# power.net
KiCad netlist of a schematic drawn in Altium Designer
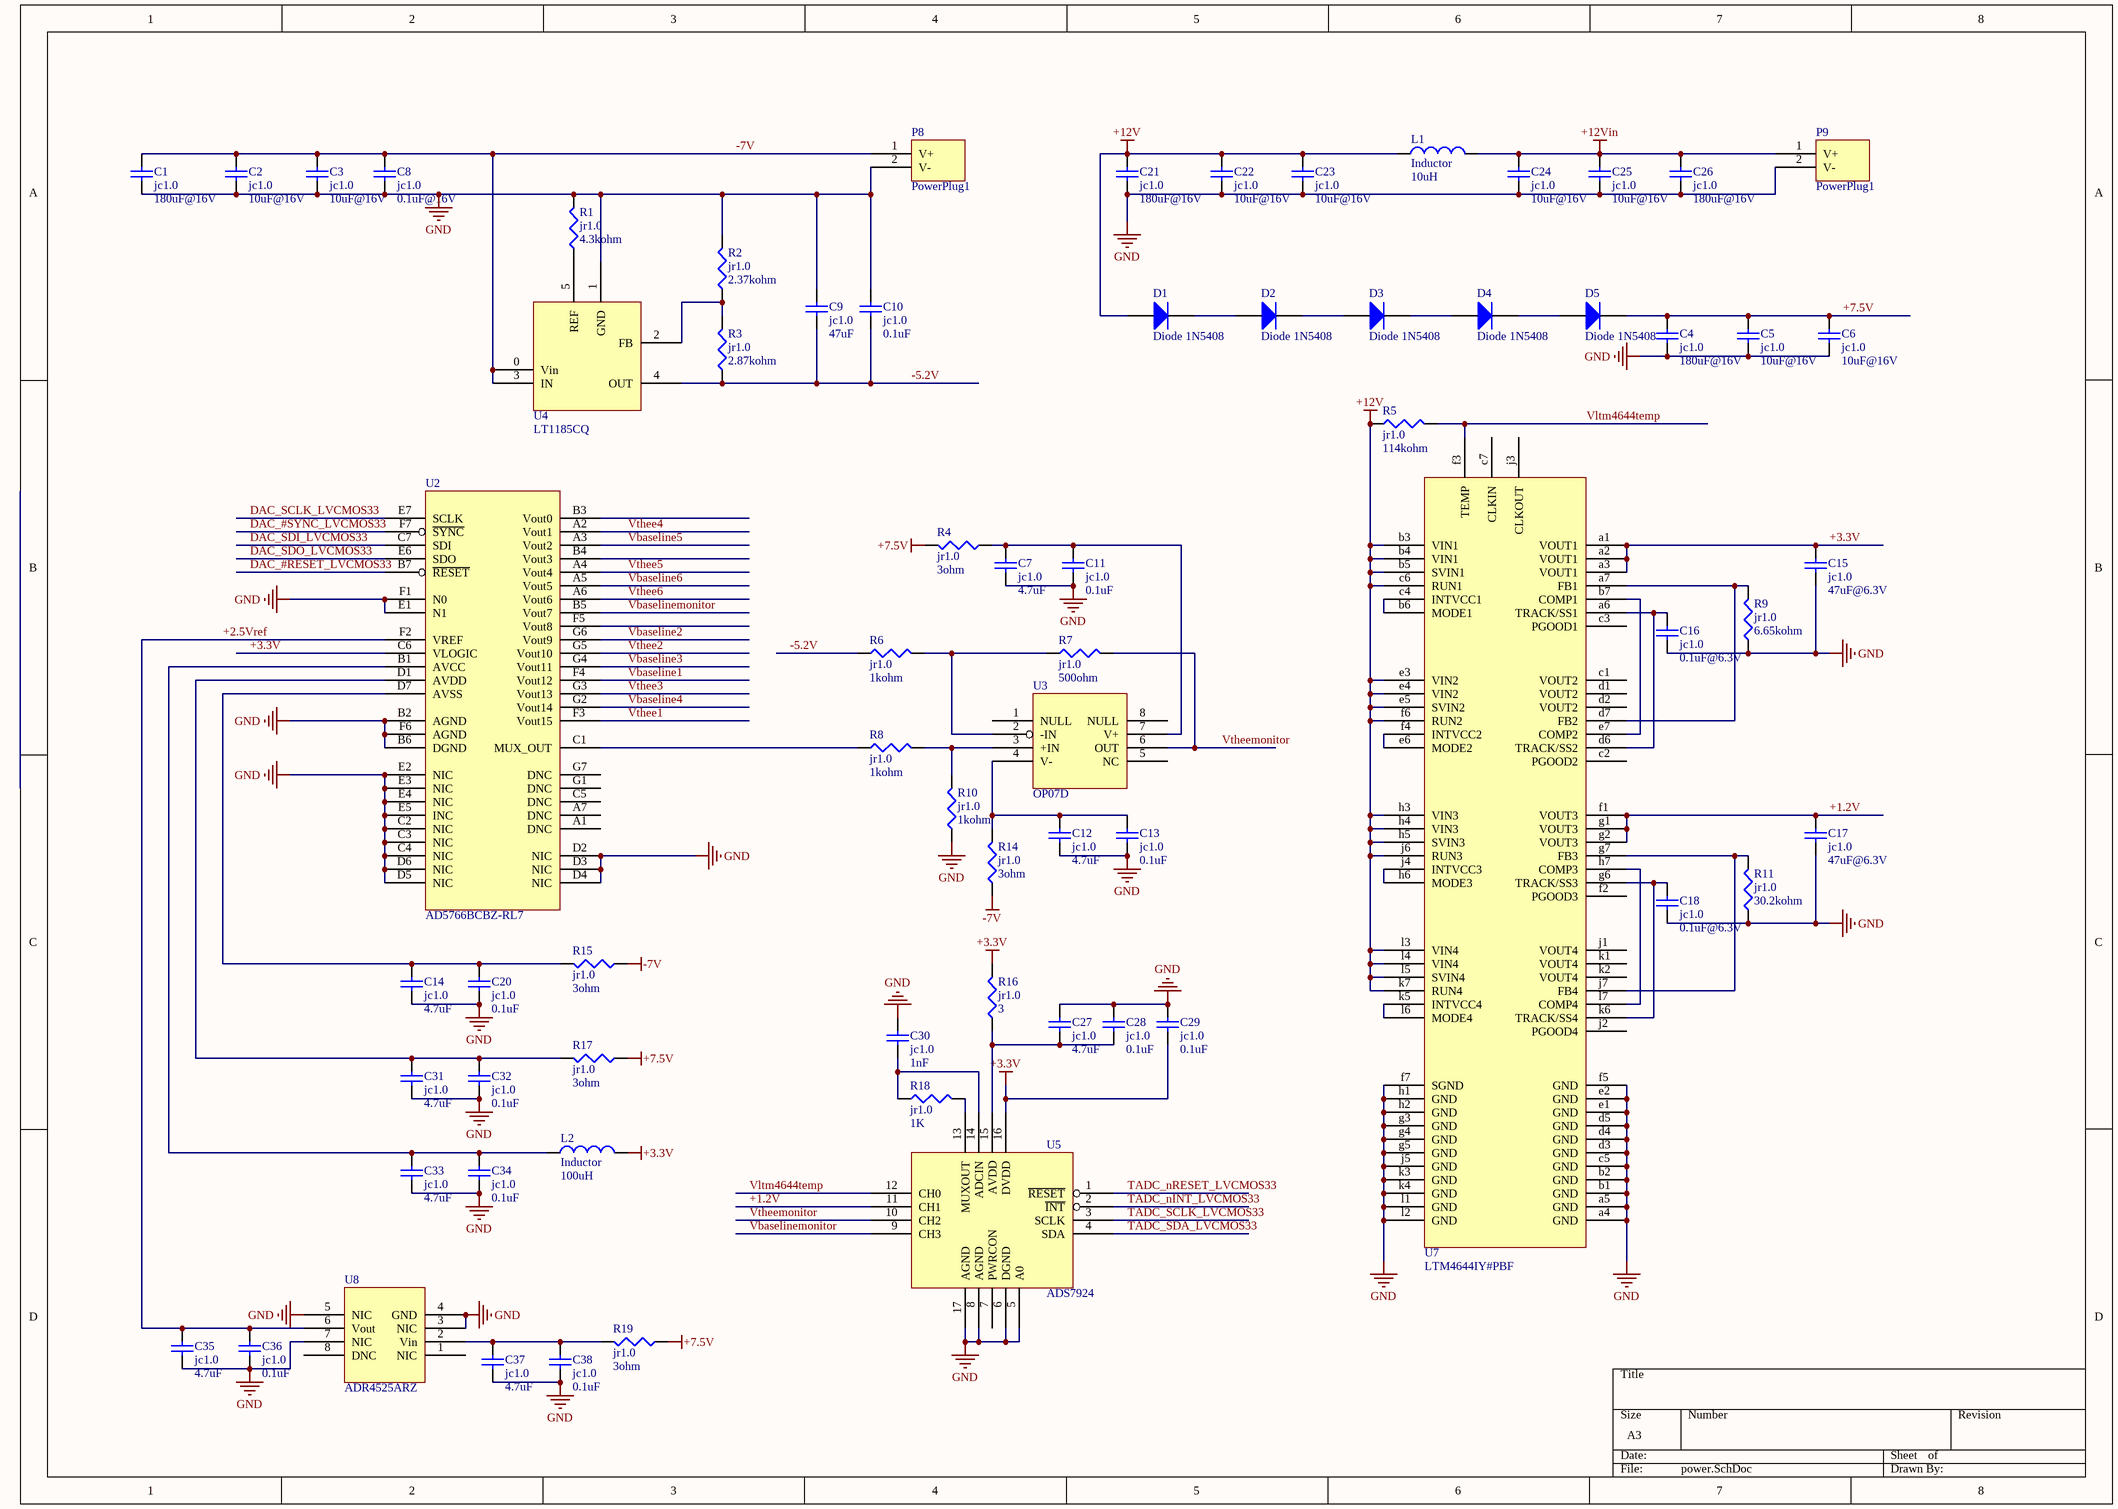
[diagram p0: power.SchDoc]

(export (version "E")
  (design (tool "Eeschema 10.0.6"))
  (components
    (comp (ref "C1")
      (value "jc1.0")
      (footprint "2220")
      (description "Capacitor")
      (fields (field (name "ALTIUM_VALUE") "180uF@16V") (field (name "PUBLISHER") "Altium Limited"))
      (libsource (lib "LIB01DXP2006SchLib") (part "Cap"))
    )
    (comp (ref "C2")
      (value "jc1.0")
      (footprint "2220")
      (description "Capacitor")
      (fields (field (name "ALTIUM_VALUE") "10uF@16V") (field (name "PUBLISHER") "Altium Limited"))
      (libsource (lib "LIB01DXP2006SchLib") (part "Cap"))
    )
    (comp (ref "C3")
      (value "jc1.0")
      (footprint "2220")
      (description "Capacitor")
      (fields (field (name "ALTIUM_VALUE") "10uF@16V") (field (name "PUBLISHER") "Altium Limited"))
      (libsource (lib "LIB01DXP2006SchLib") (part "Cap"))
    )
    (comp (ref "C4")
      (value "jc1.0")
      (footprint "2220")
      (description "Capacitor")
      (fields (field (name "ALTIUM_VALUE") "180uF@16V") (field (name "PUBLISHER") "Altium Limited"))
      (libsource (lib "LIB01DXP2006SchLib") (part "Cap"))
    )
    (comp (ref "C5")
      (value "jc1.0")
      (footprint "2220")
      (description "Capacitor")
      (fields (field (name "ALTIUM_VALUE") "10uF@16V") (field (name "PUBLISHER") "Altium Limited"))
      (libsource (lib "LIB01DXP2006SchLib") (part "Cap"))
    )
    (comp (ref "C6")
      (value "jc1.0")
      (footprint "2220")
      (description "Capacitor")
      (fields (field (name "ALTIUM_VALUE") "10uF@16V") (field (name "PUBLISHER") "Altium Limited"))
      (libsource (lib "LIB01DXP2006SchLib") (part "Cap"))
    )
    (comp (ref "C7")
      (value "jc1.0")
      (footprint "0603")
      (description "Capacitor")
      (fields (field (name "ALTIUM_VALUE") "4.7uF") (field (name "PUBLISHER") "Altium Limited"))
      (libsource (lib "LIB01DXP2006SchLib") (part "Cap"))
    )
    (comp (ref "C8")
      (value "jc1.0")
      (footprint "0805")
      (description "Capacitor")
      (fields (field (name "ALTIUM_VALUE") "0.1uF@16V") (field (name "PUBLISHER") "Altium Limited"))
      (libsource (lib "LIB01DXP2006SchLib") (part "Cap"))
    )
    (comp (ref "C9")
      (value "jc1.0")
      (footprint "2220")
      (description "Capacitor")
      (fields (field (name "ALTIUM_VALUE") "47uF") (field (name "PUBLISHER") "Altium Limited"))
      (libsource (lib "LIB01DXP2006SchLib") (part "Cap"))
    )
    (comp (ref "C10")
      (value "jc1.0")
      (footprint "2220")
      (description "Capacitor")
      (fields (field (name "ALTIUM_VALUE") "0.1uF") (field (name "PUBLISHER") "Altium Limited"))
      (libsource (lib "LIB01DXP2006SchLib") (part "Cap"))
    )
    (comp (ref "C11")
      (value "jc1.0")
      (footprint "0603")
      (description "Capacitor")
      (fields (field (name "ALTIUM_VALUE") "0.1uF") (field (name "PUBLISHER") "Altium Limited"))
      (libsource (lib "LIB01DXP2006SchLib") (part "Cap"))
    )
    (comp (ref "C12")
      (value "jc1.0")
      (footprint "0603")
      (description "Capacitor")
      (fields (field (name "ALTIUM_VALUE") "4.7uF") (field (name "PUBLISHER") "Altium Limited"))
      (libsource (lib "LIB01DXP2006SchLib") (part "Cap"))
    )
    (comp (ref "C13")
      (value "jc1.0")
      (footprint "0603")
      (description "Capacitor")
      (fields (field (name "ALTIUM_VALUE") "0.1uF") (field (name "PUBLISHER") "Altium Limited"))
      (libsource (lib "LIB01DXP2006SchLib") (part "Cap"))
    )
    (comp (ref "C14")
      (value "jc1.0")
      (footprint "0603")
      (description "Capacitor")
      (fields (field (name "ALTIUM_VALUE") "4.7uF") (field (name "PUBLISHER") "Altium Limited"))
      (libsource (lib "LIB01DXP2006SchLib") (part "Cap"))
    )
    (comp (ref "C15")
      (value "jc1.0")
      (footprint "0805")
      (description "Capacitor")
      (fields (field (name "ALTIUM_VALUE") "47uF@6.3V") (field (name "PUBLISHER") "Altium Limited"))
      (libsource (lib "LIB01DXP2006SchLib") (part "Cap"))
    )
    (comp (ref "C16")
      (value "jc1.0")
      (footprint "0402")
      (description "Capacitor")
      (fields (field (name "ALTIUM_VALUE") "0.1uF@6.3V") (field (name "PUBLISHER") "Altium Limited"))
      (libsource (lib "LIB01DXP2006SchLib") (part "Cap"))
    )
    (comp (ref "C17")
      (value "jc1.0")
      (footprint "0805")
      (description "Capacitor")
      (fields (field (name "ALTIUM_VALUE") "47uF@6.3V") (field (name "PUBLISHER") "Altium Limited"))
      (libsource (lib "LIB01DXP2006SchLib") (part "Cap"))
    )
    (comp (ref "C18")
      (value "jc1.0")
      (footprint "0402")
      (description "Capacitor")
      (fields (field (name "ALTIUM_VALUE") "0.1uF@6.3V") (field (name "PUBLISHER") "Altium Limited"))
      (libsource (lib "LIB01DXP2006SchLib") (part "Cap"))
    )
    (comp (ref "C20")
      (value "jc1.0")
      (footprint "0603")
      (description "Capacitor")
      (fields (field (name "ALTIUM_VALUE") "0.1uF") (field (name "PUBLISHER") "Altium Limited"))
      (libsource (lib "LIB01DXP2006SchLib") (part "Cap"))
    )
    (comp (ref "C21")
      (value "jc1.0")
      (footprint "2220")
      (description "Capacitor")
      (fields (field (name "ALTIUM_VALUE") "180uF@16V") (field (name "PUBLISHER") "Altium Limited"))
      (libsource (lib "LIB01DXP2006SchLib") (part "Cap"))
    )
    (comp (ref "C22")
      (value "jc1.0")
      (footprint "2220")
      (description "Capacitor")
      (fields (field (name "ALTIUM_VALUE") "10uF@16V") (field (name "PUBLISHER") "Altium Limited"))
      (libsource (lib "LIB01DXP2006SchLib") (part "Cap"))
    )
    (comp (ref "C23")
      (value "jc1.0")
      (footprint "2220")
      (description "Capacitor")
      (fields (field (name "ALTIUM_VALUE") "10uF@16V") (field (name "PUBLISHER") "Altium Limited"))
      (libsource (lib "LIB01DXP2006SchLib") (part "Cap"))
    )
    (comp (ref "C24")
      (value "jc1.0")
      (footprint "2220")
      (description "Capacitor")
      (fields (field (name "ALTIUM_VALUE") "10uF@16V") (field (name "PUBLISHER") "Altium Limited"))
      (libsource (lib "LIB01DXP2006SchLib") (part "Cap"))
    )
    (comp (ref "C25")
      (value "jc1.0")
      (footprint "2220")
      (description "Capacitor")
      (fields (field (name "ALTIUM_VALUE") "10uF@16V") (field (name "PUBLISHER") "Altium Limited"))
      (libsource (lib "LIB01DXP2006SchLib") (part "Cap"))
    )
    (comp (ref "C26")
      (value "jc1.0")
      (footprint "2220")
      (description "Capacitor")
      (fields (field (name "ALTIUM_VALUE") "180uF@16V") (field (name "PUBLISHER") "Altium Limited"))
      (libsource (lib "LIB01DXP2006SchLib") (part "Cap"))
    )
    (comp (ref "C27")
      (value "jc1.0")
      (footprint "0201")
      (description "Capacitor")
      (fields (field (name "ALTIUM_VALUE") "4.7uF") (field (name "PUBLISHER") "Altium Limited"))
      (libsource (lib "LIB01DXP2006SchLib") (part "Cap"))
    )
    (comp (ref "C28")
      (value "jc1.0")
      (footprint "0201")
      (description "Capacitor")
      (fields (field (name "ALTIUM_VALUE") "0.1uF") (field (name "PUBLISHER") "Altium Limited"))
      (libsource (lib "LIB01DXP2006SchLib") (part "Cap"))
    )
    (comp (ref "C29")
      (value "jc1.0")
      (footprint "0201")
      (description "Capacitor")
      (fields (field (name "ALTIUM_VALUE") "0.1uF") (field (name "PUBLISHER") "Altium Limited"))
      (libsource (lib "LIB01DXP2006SchLib") (part "Cap"))
    )
    (comp (ref "C30")
      (value "jc1.0")
      (footprint "0201")
      (description "Capacitor")
      (fields (field (name "ALTIUM_VALUE") "1nF") (field (name "PUBLISHER") "Altium Limited"))
      (libsource (lib "LIB01DXP2006SchLib") (part "Cap"))
    )
    (comp (ref "C31")
      (value "jc1.0")
      (footprint "0603")
      (description "Capacitor")
      (fields (field (name "ALTIUM_VALUE") "4.7uF") (field (name "PUBLISHER") "Altium Limited"))
      (libsource (lib "LIB01DXP2006SchLib") (part "Cap"))
    )
    (comp (ref "C32")
      (value "jc1.0")
      (footprint "0603")
      (description "Capacitor")
      (fields (field (name "ALTIUM_VALUE") "0.1uF") (field (name "PUBLISHER") "Altium Limited"))
      (libsource (lib "LIB01DXP2006SchLib") (part "Cap"))
    )
    (comp (ref "C33")
      (value "jc1.0")
      (footprint "0603")
      (description "Capacitor")
      (fields (field (name "ALTIUM_VALUE") "4.7uF") (field (name "PUBLISHER") "Altium Limited"))
      (libsource (lib "LIB01DXP2006SchLib") (part "Cap"))
    )
    (comp (ref "C34")
      (value "jc1.0")
      (footprint "0603")
      (description "Capacitor")
      (fields (field (name "ALTIUM_VALUE") "0.1uF") (field (name "PUBLISHER") "Altium Limited"))
      (libsource (lib "LIB01DXP2006SchLib") (part "Cap"))
    )
    (comp (ref "C35")
      (value "jc1.0")
      (footprint "0603")
      (description "Capacitor")
      (fields (field (name "ALTIUM_VALUE") "4.7uF") (field (name "PUBLISHER") "Altium Limited"))
      (libsource (lib "LIB01DXP2006SchLib") (part "Cap"))
    )
    (comp (ref "C36")
      (value "jc1.0")
      (footprint "0603")
      (description "Capacitor")
      (fields (field (name "ALTIUM_VALUE") "0.1uF") (field (name "PUBLISHER") "Altium Limited"))
      (libsource (lib "LIB01DXP2006SchLib") (part "Cap"))
    )
    (comp (ref "C37")
      (value "jc1.0")
      (footprint "0603")
      (description "Capacitor")
      (fields (field (name "ALTIUM_VALUE") "4.7uF") (field (name "PUBLISHER") "Altium Limited"))
      (libsource (lib "LIB01DXP2006SchLib") (part "Cap"))
    )
    (comp (ref "C38")
      (value "jc1.0")
      (footprint "0603")
      (description "Capacitor")
      (fields (field (name "ALTIUM_VALUE") "0.1uF") (field (name "PUBLISHER") "Altium Limited"))
      (libsource (lib "LIB01DXP2006SchLib") (part "Cap"))
    )
    (comp (ref "D1")
      (value "Diode 1N5408")
      (footprint "DO-201AD")
      (description "3 Amp Medium Power Silicon Rectifier Diode")
      (fields (field (name "PUBLISHER") "Altium Limited"))
      (libsource (lib "Miscellaneous Devices") (part "Diode 1N5408"))
    )
    (comp (ref "D2")
      (value "Diode 1N5408")
      (footprint "DO-201AD")
      (description "3 Amp Medium Power Silicon Rectifier Diode")
      (fields (field (name "PUBLISHER") "Altium Limited"))
      (libsource (lib "Miscellaneous Devices") (part "Diode 1N5408"))
    )
    (comp (ref "D3")
      (value "Diode 1N5408")
      (footprint "DO-201AD")
      (description "3 Amp Medium Power Silicon Rectifier Diode")
      (fields (field (name "PUBLISHER") "Altium Limited"))
      (libsource (lib "Miscellaneous Devices") (part "Diode 1N5408"))
    )
    (comp (ref "D4")
      (value "Diode 1N5408")
      (footprint "DO-201AD")
      (description "3 Amp Medium Power Silicon Rectifier Diode")
      (fields (field (name "PUBLISHER") "Altium Limited"))
      (libsource (lib "Miscellaneous Devices") (part "Diode 1N5408"))
    )
    (comp (ref "D5")
      (value "Diode 1N5408")
      (footprint "DO-201AD")
      (description "3 Amp Medium Power Silicon Rectifier Diode")
      (fields (field (name "PUBLISHER") "Altium Limited"))
      (libsource (lib "Miscellaneous Devices") (part "Diode 1N5408"))
    )
    (comp (ref "L1")
      (value "Inductor")
      (footprint "AXIAL0.3 - 35")
      (fields (field (name "ALTIUM_VALUE") "10uH") (field (name "PUBLISHER") "Altium Limited"))
      (libsource (lib "LIB01DXP2006SchLib") (part "Inductor"))
    )
    (comp (ref "L2")
      (value "Inductor")
      (footprint "0805")
      (fields (field (name "ALTIUM_VALUE") "100uH") (field (name "PUBLISHER") "Altium Limited"))
      (libsource (lib "LIB01DXP2006SchLib") (part "Inductor"))
    )
    (comp (ref "P8")
      (value "PowerPlug1")
      (footprint "POWERPLUG1")
      (libsource (lib "LIB01DXP2006SchLib") (part "PowerPlug1"))
    )
    (comp (ref "P9")
      (value "PowerPlug1")
      (footprint "POWERPLUG1")
      (libsource (lib "LIB01DXP2006SchLib") (part "PowerPlug1"))
    )
    (comp (ref "R1")
      (value "jr1.0")
      (footprint "0805")
      (description "Resistor")
      (fields (field (name "ALTIUM_VALUE") "4.3kohm") (field (name "PUBLISHER") "Altium Limited"))
      (libsource (lib "LIB01DXP2006SchLib") (part "Res"))
    )
    (comp (ref "R2")
      (value "jr1.0")
      (footprint "0805")
      (description "Resistor")
      (fields (field (name "ALTIUM_VALUE") "2.37kohm") (field (name "PUBLISHER") "Altium Limited"))
      (libsource (lib "LIB01DXP2006SchLib") (part "Res"))
    )
    (comp (ref "R3")
      (value "jr1.0")
      (footprint "0805")
      (description "Resistor")
      (fields (field (name "ALTIUM_VALUE") "2.87kohm") (field (name "PUBLISHER") "Altium Limited"))
      (libsource (lib "LIB01DXP2006SchLib") (part "Res"))
    )
    (comp (ref "R4")
      (value "jr1.0")
      (footprint "0603")
      (description "Resistor")
      (fields (field (name "ALTIUM_VALUE") "3ohm") (field (name "PUBLISHER") "Altium Limited"))
      (libsource (lib "LIB01DXP2006SchLib") (part "Res"))
    )
    (comp (ref "R5")
      (value "jr1.0")
      (footprint "0402")
      (description "Resistor")
      (fields (field (name "ALTIUM_VALUE") "114kohm") (field (name "PUBLISHER") "Altium Limited"))
      (libsource (lib "LIB01DXP2006SchLib") (part "Res"))
    )
    (comp (ref "R6")
      (value "jr1.0")
      (footprint "0603")
      (description "Resistor")
      (fields (field (name "ALTIUM_VALUE") "1kohm") (field (name "PUBLISHER") "Altium Limited"))
      (libsource (lib "LIB01DXP2006SchLib") (part "Res"))
    )
    (comp (ref "R7")
      (value "jr1.0")
      (footprint "0603")
      (description "Resistor")
      (fields (field (name "ALTIUM_VALUE") "500ohm") (field (name "PUBLISHER") "Altium Limited"))
      (libsource (lib "LIB01DXP2006SchLib") (part "Res"))
    )
    (comp (ref "R8")
      (value "jr1.0")
      (footprint "0603")
      (description "Resistor")
      (fields (field (name "ALTIUM_VALUE") "1kohm") (field (name "PUBLISHER") "Altium Limited"))
      (libsource (lib "LIB01DXP2006SchLib") (part "Res"))
    )
    (comp (ref "R9")
      (value "jr1.0")
      (footprint "0805")
      (description "Resistor")
      (fields (field (name "ALTIUM_VALUE") "6.65kohm") (field (name "PUBLISHER") "Altium Limited"))
      (libsource (lib "LIB01DXP2006SchLib") (part "Res"))
    )
    (comp (ref "R10")
      (value "jr1.0")
      (footprint "0603")
      (description "Resistor")
      (fields (field (name "ALTIUM_VALUE") "1kohm") (field (name "PUBLISHER") "Altium Limited"))
      (libsource (lib "LIB01DXP2006SchLib") (part "Res"))
    )
    (comp (ref "R11")
      (value "jr1.0")
      (footprint "0805")
      (description "Resistor")
      (fields (field (name "ALTIUM_VALUE") "30.2kohm") (field (name "PUBLISHER") "Altium Limited"))
      (libsource (lib "LIB01DXP2006SchLib") (part "Res"))
    )
    (comp (ref "R14")
      (value "jr1.0")
      (footprint "0603")
      (description "Resistor")
      (fields (field (name "ALTIUM_VALUE") "3ohm") (field (name "PUBLISHER") "Altium Limited"))
      (libsource (lib "LIB01DXP2006SchLib") (part "Res"))
    )
    (comp (ref "R15")
      (value "jr1.0")
      (footprint "0603")
      (description "Resistor")
      (fields (field (name "ALTIUM_VALUE") "3ohm") (field (name "PUBLISHER") "Altium Limited"))
      (libsource (lib "LIB01DXP2006SchLib") (part "Res"))
    )
    (comp (ref "R16")
      (value "jr1.0")
      (footprint "0201")
      (description "Resistor")
      (fields (field (name "ALTIUM_VALUE") "3") (field (name "PUBLISHER") "Altium Limited"))
      (libsource (lib "LIB01DXP2006SchLib") (part "Res"))
    )
    (comp (ref "R17")
      (value "jr1.0")
      (footprint "0603")
      (description "Resistor")
      (fields (field (name "ALTIUM_VALUE") "3ohm") (field (name "PUBLISHER") "Altium Limited"))
      (libsource (lib "LIB01DXP2006SchLib") (part "Res"))
    )
    (comp (ref "R18")
      (value "jr1.0")
      (footprint "0201")
      (description "Resistor")
      (fields (field (name "ALTIUM_VALUE") "1K") (field (name "PUBLISHER") "Altium Limited"))
      (libsource (lib "LIB01DXP2006SchLib") (part "Res"))
    )
    (comp (ref "R19")
      (value "jr1.0")
      (footprint "0603")
      (description "Resistor")
      (fields (field (name "ALTIUM_VALUE") "3ohm") (field (name "PUBLISHER") "Altium Limited"))
      (libsource (lib "LIB01DXP2006SchLib") (part "Res"))
    )
    (comp (ref "U2")
      (value "AD5766BCBZ-RL7")
      (footprint "WLCSP-49")
      (libsource (lib "LIB01DXP2006SchLib") (part "AD5766BCBZ-RL7"))
    )
    (comp (ref "U3")
      (value "OP07D")
      (footprint "R8(SOP127P600-8N)")
      (libsource (lib "LIB01DXP2006SchLib") (part "OP07D"))
    )
    (comp (ref "U4")
      (value "LT1185CQ")
      (footprint "LP5 - 1185")
      (libsource (lib "LIB01DXP2006SchLib") (part "LT1185CQ"))
    )
    (comp (ref "U5")
      (value "ADS7924")
      (footprint "QFN50P300X300X80_HS-17N")
      (libsource (lib "LIB01DXP2006SchLib") (part "ADS7924"))
    )
    (comp (ref "U7")
      (value "LTM4644IY#PBF")
      (footprint "BGA77C127P7X11_900X1500X521")
      (libsource (lib "LIB01DXP2006SchLib") (part "LTM4644IY#PBF"))
    )
    (comp (ref "U8")
      (value "ADR4525ARZ")
      (footprint "R8(SOP127P600-8N)")
      (libsource (lib "LIB01DXP2006SchLib") (part "ADR4525BRZ"))
    )
  )
  (nets
    (net (code "1") (name "+3.3V") (class "Default")
      (node (ref "C15") (pin "2") (pinfunction "2_2") (pintype "passive"))
      (node (ref "C29") (pin "1") (pinfunction "1_1") (pintype "passive"))
      (node (ref "L2") (pin "2") (pinfunction "2_2") (pintype "passive"))
      (node (ref "R16") (pin "2") (pinfunction "2_2") (pintype "passive"))
      (node (ref "U2") (pin "C6") (pinfunction "VLOGIC_C6") (pintype "passive"))
      (node (ref "U5") (pin "16") (pinfunction "DVDD_16") (pintype "passive"))
      (node (ref "U7") (pin "a1") (pinfunction "VOUT1_a1") (pintype "passive"))
      (node (ref "U7") (pin "a2") (pinfunction "VOUT1_a2") (pintype "passive"))
      (node (ref "U7") (pin "a3") (pinfunction "VOUT1_a3") (pintype "passive"))
    )
    (net (code "2") (name "+7.5V") (class "Default")
      (node (ref "C4") (pin "2") (pinfunction "2_2") (pintype "passive"))
      (node (ref "C5") (pin "2") (pinfunction "2_2") (pintype "passive"))
      (node (ref "C6") (pin "2") (pinfunction "2_2") (pintype "passive"))
      (node (ref "D5") (pin "2") (pinfunction "K_2") (pintype "passive"))
      (node (ref "R17") (pin "1") (pinfunction "1_1") (pintype "passive"))
      (node (ref "R19") (pin "1") (pinfunction "1_1") (pintype "passive"))
      (node (ref "R4") (pin "2") (pinfunction "2_2") (pintype "passive"))
    )
    (net (code "3") (name "+12V") (class "Default")
      (node (ref "C21") (pin "2") (pinfunction "2_2") (pintype "passive"))
      (node (ref "C22") (pin "2") (pinfunction "2_2") (pintype "passive"))
      (node (ref "C23") (pin "2") (pinfunction "2_2") (pintype "passive"))
      (node (ref "D1") (pin "1") (pinfunction "A_1") (pintype "passive"))
      (node (ref "L1") (pin "1") (pinfunction "1_1") (pintype "passive"))
      (node (ref "R5") (pin "1") (pinfunction "1_1") (pintype "passive"))
      (node (ref "U7") (pin "b3") (pinfunction "VIN1_b3") (pintype "passive"))
      (node (ref "U7") (pin "b4") (pinfunction "VIN1_b4") (pintype "passive"))
      (node (ref "U7") (pin "b5") (pinfunction "SVIN1_b5") (pintype "passive"))
      (node (ref "U7") (pin "c6") (pinfunction "RUN1_c6") (pintype "passive"))
      (node (ref "U7") (pin "e3") (pinfunction "VIN2_e3") (pintype "passive"))
      (node (ref "U7") (pin "e4") (pinfunction "VIN2_e4") (pintype "passive"))
      (node (ref "U7") (pin "e5") (pinfunction "SVIN2_e5") (pintype "passive"))
      (node (ref "U7") (pin "f6") (pinfunction "RUN2_f6") (pintype "passive"))
      (node (ref "U7") (pin "h3") (pinfunction "VIN3_h3") (pintype "passive"))
      (node (ref "U7") (pin "h4") (pinfunction "VIN3_h4") (pintype "passive"))
      (node (ref "U7") (pin "h5") (pinfunction "SVIN3_h5") (pintype "passive"))
      (node (ref "U7") (pin "j6") (pinfunction "RUN3_j6") (pintype "passive"))
      (node (ref "U7") (pin "k7") (pinfunction "RUN4_k7") (pintype "passive"))
      (node (ref "U7") (pin "l3") (pinfunction "VIN4_l3") (pintype "passive"))
      (node (ref "U7") (pin "l4") (pinfunction "VIN4_l4") (pintype "passive"))
      (node (ref "U7") (pin "l5") (pinfunction "SVIN4_l5") (pintype "passive"))
    )
    (net (code "4") (name "+12Vin") (class "Default")
      (node (ref "C24") (pin "2") (pinfunction "2_2") (pintype "passive"))
      (node (ref "C25") (pin "2") (pinfunction "2_2") (pintype "passive"))
      (node (ref "C26") (pin "2") (pinfunction "2_2") (pintype "passive"))
      (node (ref "L1") (pin "2") (pinfunction "2_2") (pintype "passive"))
      (node (ref "P9") (pin "1") (pinfunction "V+_1") (pintype "passive"))
    )
    (net (code "5") (name "-7V") (class "Default")
      (node (ref "C1") (pin "2") (pinfunction "2_2") (pintype "passive"))
      (node (ref "C2") (pin "2") (pinfunction "2_2") (pintype "passive"))
      (node (ref "C3") (pin "2") (pinfunction "2_2") (pintype "passive"))
      (node (ref "C8") (pin "2") (pinfunction "2_2") (pintype "passive"))
      (node (ref "P8") (pin "1") (pinfunction "V+_1") (pintype "passive"))
      (node (ref "R14") (pin "1") (pinfunction "1_1") (pintype "passive"))
      (node (ref "R15") (pin "1") (pinfunction "1_1") (pintype "passive"))
      (node (ref "U4") (pin "0") (pinfunction "Vin_0") (pintype "passive"))
      (node (ref "U4") (pin "3") (pinfunction "IN_3") (pintype "passive"))
    )
    (net (code "6") (name "/+1.2V") (class "Default")
      (node (ref "C17") (pin "2") (pinfunction "2_2") (pintype "passive"))
      (node (ref "U5") (pin "11") (pinfunction "CH1_11") (pintype "passive"))
      (node (ref "U7") (pin "f1") (pinfunction "VOUT3_f1") (pintype "passive"))
      (node (ref "U7") (pin "g1") (pinfunction "VOUT3_g1") (pintype "passive"))
      (node (ref "U7") (pin "g2") (pinfunction "VOUT3_g2") (pintype "passive"))
    )
    (net (code "7") (name "/+2.5Vref") (class "Default")
      (node (ref "C35") (pin "2") (pinfunction "2_2") (pintype "passive"))
      (node (ref "C36") (pin "2") (pinfunction "2_2") (pintype "passive"))
      (node (ref "U2") (pin "F2") (pinfunction "VREF_F2") (pintype "passive"))
      (node (ref "U8") (pin "6") (pinfunction "Vout_6") (pintype "passive"))
    )
    (net (code "8") (name "/-5.2V") (class "Default")
      (node (ref "C10") (pin "1") (pinfunction "1_1") (pintype "passive"))
      (node (ref "C9") (pin "1") (pinfunction "1_1") (pintype "passive"))
      (node (ref "R3") (pin "1") (pinfunction "1_1") (pintype "passive"))
      (node (ref "R6") (pin "1") (pinfunction "1_1") (pintype "passive"))
      (node (ref "U4") (pin "4") (pinfunction "OUT_4") (pintype "passive"))
    )
    (net (code "9") (name "/DAC_#RESET_LVCMOS33") (class "Default")
      (node (ref "U2") (pin "B7") (pinfunction "~{RESET}_B7") (pintype "passive"))
    )
    (net (code "10") (name "/DAC_#SYNC_LVCMOS33") (class "Default")
      (node (ref "U2") (pin "F7") (pinfunction "~{SYNC}_F7") (pintype "passive"))
    )
    (net (code "11") (name "/DAC_SCLK_LVCMOS33") (class "Default")
      (node (ref "U2") (pin "E7") (pinfunction "SCLK_E7") (pintype "passive"))
    )
    (net (code "12") (name "/DAC_SDI_LVCMOS33") (class "Default")
      (node (ref "U2") (pin "C7") (pinfunction "SDI_C7") (pintype "passive"))
    )
    (net (code "13") (name "/DAC_SDO_LVCMOS33") (class "Default")
      (node (ref "U2") (pin "E6") (pinfunction "SDO_E6") (pintype "passive"))
    )
    (net (code "14") (name "/TADC_SCLK_LVCMOS33") (class "Default")
      (node (ref "U5") (pin "3") (pinfunction "SCLK_3") (pintype "passive"))
    )
    (net (code "15") (name "/TADC_SDA_LVCMOS33") (class "Default")
      (node (ref "U5") (pin "4") (pinfunction "SDA_4") (pintype "passive"))
    )
    (net (code "16") (name "/TADC_nINT_LVCMOS33") (class "Default")
      (node (ref "U5") (pin "2") (pinfunction "~{INT}_2") (pintype "passive"))
    )
    (net (code "17") (name "/TADC_nRESET_LVCMOS33") (class "Default")
      (node (ref "U5") (pin "1") (pinfunction "~{RESET}_1") (pintype "passive"))
    )
    (net (code "18") (name "/Vbaseline1") (class "Default")
      (node (ref "U2") (pin "F4") (pinfunction "Vout12_F4") (pintype "passive"))
    )
    (net (code "19") (name "/Vbaseline2") (class "Default")
      (node (ref "U2") (pin "G6") (pinfunction "Vout9_G6") (pintype "passive"))
    )
    (net (code "20") (name "/Vbaseline3") (class "Default")
      (node (ref "U2") (pin "G4") (pinfunction "Vout11_G4") (pintype "passive"))
    )
    (net (code "21") (name "/Vbaseline4") (class "Default")
      (node (ref "U2") (pin "G2") (pinfunction "Vout14_G2") (pintype "passive"))
    )
    (net (code "22") (name "/Vbaseline5") (class "Default")
      (node (ref "U2") (pin "A3") (pinfunction "Vout2_A3") (pintype "passive"))
    )
    (net (code "23") (name "/Vbaseline6") (class "Default")
      (node (ref "U2") (pin "A5") (pinfunction "Vout5_A5") (pintype "passive"))
    )
    (net (code "24") (name "/Vbaselinemonitor") (class "Default")
      (node (ref "U2") (pin "B5") (pinfunction "Vout7_B5") (pintype "passive"))
      (node (ref "U5") (pin "9") (pinfunction "CH3_9") (pintype "passive"))
    )
    (net (code "25") (name "/Vltm4644temp") (class "Default")
      (node (ref "R5") (pin "2") (pinfunction "2_2") (pintype "passive"))
      (node (ref "U5") (pin "12") (pinfunction "CH0_12") (pintype "passive"))
      (node (ref "U7") (pin "f3") (pinfunction "TEMP_f3") (pintype "passive"))
    )
    (net (code "26") (name "/Vthee1") (class "Default")
      (node (ref "U2") (pin "F3") (pinfunction "Vout15_F3") (pintype "passive"))
    )
    (net (code "27") (name "/Vthee2") (class "Default")
      (node (ref "U2") (pin "G5") (pinfunction "Vout10_G5") (pintype "passive"))
    )
    (net (code "28") (name "/Vthee3") (class "Default")
      (node (ref "U2") (pin "G3") (pinfunction "Vout13_G3") (pintype "passive"))
    )
    (net (code "29") (name "/Vthee4") (class "Default")
      (node (ref "U2") (pin "A2") (pinfunction "Vout1_A2") (pintype "passive"))
    )
    (net (code "30") (name "/Vthee5") (class "Default")
      (node (ref "U2") (pin "A4") (pinfunction "Vout4_A4") (pintype "passive"))
    )
    (net (code "31") (name "/Vthee6") (class "Default")
      (node (ref "U2") (pin "A6") (pinfunction "Vout6_A6") (pintype "passive"))
    )
    (net (code "32") (name "/Vtheemonitor") (class "Default")
      (node (ref "R7") (pin "2") (pinfunction "2_2") (pintype "passive"))
      (node (ref "U3") (pin "6") (pinfunction "OUT_6") (pintype "passive"))
      (node (ref "U5") (pin "10") (pinfunction "CH2_10") (pintype "passive"))
    )
    (net (code "33") (name "GND") (class "Default")
      (node (ref "C1") (pin "1") (pinfunction "1_1") (pintype "passive"))
      (node (ref "C10") (pin "2") (pinfunction "2_2") (pintype "passive"))
      (node (ref "C11") (pin "1") (pinfunction "1_1") (pintype "passive"))
      (node (ref "C12") (pin "1") (pinfunction "1_1") (pintype "passive"))
      (node (ref "C13") (pin "1") (pinfunction "1_1") (pintype "passive"))
      (node (ref "C14") (pin "1") (pinfunction "1_1") (pintype "passive"))
      (node (ref "C15") (pin "1") (pinfunction "1_1") (pintype "passive"))
      (node (ref "C16") (pin "1") (pinfunction "1_1") (pintype "passive"))
      (node (ref "C17") (pin "1") (pinfunction "1_1") (pintype "passive"))
      (node (ref "C18") (pin "1") (pinfunction "1_1") (pintype "passive"))
      (node (ref "C2") (pin "1") (pinfunction "1_1") (pintype "passive"))
      (node (ref "C20") (pin "1") (pinfunction "1_1") (pintype "passive"))
      (node (ref "C21") (pin "1") (pinfunction "1_1") (pintype "passive"))
      (node (ref "C22") (pin "1") (pinfunction "1_1") (pintype "passive"))
      (node (ref "C23") (pin "1") (pinfunction "1_1") (pintype "passive"))
      (node (ref "C24") (pin "1") (pinfunction "1_1") (pintype "passive"))
      (node (ref "C25") (pin "1") (pinfunction "1_1") (pintype "passive"))
      (node (ref "C26") (pin "1") (pinfunction "1_1") (pintype "passive"))
      (node (ref "C27") (pin "2") (pinfunction "2_2") (pintype "passive"))
      (node (ref "C28") (pin "2") (pinfunction "2_2") (pintype "passive"))
      (node (ref "C29") (pin "2") (pinfunction "2_2") (pintype "passive"))
      (node (ref "C3") (pin "1") (pinfunction "1_1") (pintype "passive"))
      (node (ref "C30") (pin "2") (pinfunction "2_2") (pintype "passive"))
      (node (ref "C31") (pin "1") (pinfunction "1_1") (pintype "passive"))
      (node (ref "C32") (pin "1") (pinfunction "1_1") (pintype "passive"))
      (node (ref "C33") (pin "1") (pinfunction "1_1") (pintype "passive"))
      (node (ref "C34") (pin "1") (pinfunction "1_1") (pintype "passive"))
      (node (ref "C35") (pin "1") (pinfunction "1_1") (pintype "passive"))
      (node (ref "C36") (pin "1") (pinfunction "1_1") (pintype "passive"))
      (node (ref "C37") (pin "1") (pinfunction "1_1") (pintype "passive"))
      (node (ref "C38") (pin "1") (pinfunction "1_1") (pintype "passive"))
      (node (ref "C4") (pin "1") (pinfunction "1_1") (pintype "passive"))
      (node (ref "C5") (pin "1") (pinfunction "1_1") (pintype "passive"))
      (node (ref "C6") (pin "1") (pinfunction "1_1") (pintype "passive"))
      (node (ref "C7") (pin "1") (pinfunction "1_1") (pintype "passive"))
      (node (ref "C8") (pin "1") (pinfunction "1_1") (pintype "passive"))
      (node (ref "C9") (pin "2") (pinfunction "2_2") (pintype "passive"))
      (node (ref "P8") (pin "2") (pinfunction "V-_2") (pintype "passive"))
      (node (ref "P9") (pin "2") (pinfunction "V-_2") (pintype "passive"))
      (node (ref "R1") (pin "2") (pinfunction "2_2") (pintype "passive"))
      (node (ref "R10") (pin "1") (pinfunction "1_1") (pintype "passive"))
      (node (ref "R11") (pin "1") (pinfunction "1_1") (pintype "passive"))
      (node (ref "R2") (pin "2") (pinfunction "2_2") (pintype "passive"))
      (node (ref "R9") (pin "1") (pinfunction "1_1") (pintype "passive"))
      (node (ref "U2") (pin "B2") (pinfunction "AGND_B2") (pintype "passive"))
      (node (ref "U2") (pin "B6") (pinfunction "DGND_B6") (pintype "passive"))
      (node (ref "U2") (pin "C2") (pinfunction "NIC_C2") (pintype "passive"))
      (node (ref "U2") (pin "C3") (pinfunction "NIC_C3") (pintype "passive"))
      (node (ref "U2") (pin "C4") (pinfunction "NIC_C4") (pintype "passive"))
      (node (ref "U2") (pin "D2") (pinfunction "NIC_D2") (pintype "passive"))
      (node (ref "U2") (pin "D3") (pinfunction "NIC_D3") (pintype "passive"))
      (node (ref "U2") (pin "D4") (pinfunction "NIC_D4") (pintype "passive"))
      (node (ref "U2") (pin "D5") (pinfunction "NIC_D5") (pintype "passive"))
      (node (ref "U2") (pin "D6") (pinfunction "NIC_D6") (pintype "passive"))
      (node (ref "U2") (pin "E1") (pinfunction "N1_E1") (pintype "passive"))
      (node (ref "U2") (pin "E2") (pinfunction "NIC_E2") (pintype "passive"))
      (node (ref "U2") (pin "E3") (pinfunction "NIC_E3") (pintype "passive"))
      (node (ref "U2") (pin "E4") (pinfunction "NIC_E4") (pintype "passive"))
      (node (ref "U2") (pin "E5") (pinfunction "INC_E5") (pintype "passive"))
      (node (ref "U2") (pin "F1") (pinfunction "N0_F1") (pintype "passive"))
      (node (ref "U2") (pin "F6") (pinfunction "AGND_F6") (pintype "passive"))
      (node (ref "U4") (pin "1") (pinfunction "GND_1") (pintype "passive"))
      (node (ref "U5") (pin "17") (pinfunction "AGND_17") (pintype "passive"))
      (node (ref "U5") (pin "5") (pinfunction "A0_5") (pintype "passive"))
      (node (ref "U5") (pin "6") (pinfunction "DGND_6") (pintype "passive"))
      (node (ref "U5") (pin "8") (pinfunction "AGND_8") (pintype "passive"))
      (node (ref "U7") (pin "a4") (pinfunction "GND_a4") (pintype "passive"))
      (node (ref "U7") (pin "a5") (pinfunction "GND_a5") (pintype "passive"))
      (node (ref "U7") (pin "b1") (pinfunction "GND_b1") (pintype "passive"))
      (node (ref "U7") (pin "b2") (pinfunction "GND_b2") (pintype "passive"))
      (node (ref "U7") (pin "c5") (pinfunction "GND_c5") (pintype "passive"))
      (node (ref "U7") (pin "d3") (pinfunction "GND_d3") (pintype "passive"))
      (node (ref "U7") (pin "d4") (pinfunction "GND_d4") (pintype "passive"))
      (node (ref "U7") (pin "d5") (pinfunction "GND_d5") (pintype "passive"))
      (node (ref "U7") (pin "e1") (pinfunction "GND_e1") (pintype "passive"))
      (node (ref "U7") (pin "e2") (pinfunction "GND_e2") (pintype "passive"))
      (node (ref "U7") (pin "f5") (pinfunction "GND_f5") (pintype "passive"))
      (node (ref "U7") (pin "f7") (pinfunction "SGND_f7") (pintype "passive"))
      (node (ref "U7") (pin "g3") (pinfunction "GND_g3") (pintype "passive"))
      (node (ref "U7") (pin "g4") (pinfunction "GND_g4") (pintype "passive"))
      (node (ref "U7") (pin "g5") (pinfunction "GND_g5") (pintype "passive"))
      (node (ref "U7") (pin "h1") (pinfunction "GND_h1") (pintype "passive"))
      (node (ref "U7") (pin "h2") (pinfunction "GND_h2") (pintype "passive"))
      (node (ref "U7") (pin "j5") (pinfunction "GND_j5") (pintype "passive"))
      (node (ref "U7") (pin "k3") (pinfunction "GND_k3") (pintype "passive"))
      (node (ref "U7") (pin "k4") (pinfunction "GND_k4") (pintype "passive"))
      (node (ref "U7") (pin "l1") (pinfunction "GND_l1") (pintype "passive"))
      (node (ref "U7") (pin "l2") (pinfunction "GND_l2") (pintype "passive"))
      (node (ref "U8") (pin "3") (pinfunction "NIC_3") (pintype "passive"))
      (node (ref "U8") (pin "4") (pinfunction "GND_4") (pintype "passive"))
      (node (ref "U8") (pin "5") (pinfunction "NIC_5") (pintype "passive"))
      (node (ref "U8") (pin "7") (pinfunction "NIC_7") (pintype "passive"))
    )
    (net (code "34") (name "Net-(D1-K)") (class "Default")
      (node (ref "D1") (pin "2") (pinfunction "K_2") (pintype "passive"))
      (node (ref "D2") (pin "1") (pinfunction "A_1") (pintype "passive"))
    )
    (net (code "35") (name "Net-(D2-K)") (class "Default")
      (node (ref "D2") (pin "2") (pinfunction "K_2") (pintype "passive"))
      (node (ref "D3") (pin "1") (pinfunction "A_1") (pintype "passive"))
    )
    (net (code "36") (name "Net-(D3-K)") (class "Default")
      (node (ref "D3") (pin "2") (pinfunction "K_2") (pintype "passive"))
      (node (ref "D4") (pin "1") (pinfunction "A_1") (pintype "passive"))
    )
    (net (code "37") (name "Net-(D4-K)") (class "Default")
      (node (ref "D4") (pin "2") (pinfunction "K_2") (pintype "passive"))
      (node (ref "D5") (pin "1") (pinfunction "A_1") (pintype "passive"))
    )
    (net (code "38") (name "Net-(U2-AVCC)") (class "Default")
      (node (ref "C33") (pin "2") (pinfunction "2_2") (pintype "passive"))
      (node (ref "C34") (pin "2") (pinfunction "2_2") (pintype "passive"))
      (node (ref "L2") (pin "1") (pinfunction "1_1") (pintype "passive"))
      (node (ref "U2") (pin "B1") (pinfunction "AVCC_B1") (pintype "passive"))
    )
    (net (code "39") (name "Net-(U2-AVDD)") (class "Default")
      (node (ref "C31") (pin "2") (pinfunction "2_2") (pintype "passive"))
      (node (ref "C32") (pin "2") (pinfunction "2_2") (pintype "passive"))
      (node (ref "R17") (pin "2") (pinfunction "2_2") (pintype "passive"))
      (node (ref "U2") (pin "D1") (pinfunction "AVDD_D1") (pintype "passive"))
    )
    (net (code "40") (name "Net-(U2-AVSS)") (class "Default")
      (node (ref "C14") (pin "2") (pinfunction "2_2") (pintype "passive"))
      (node (ref "C20") (pin "2") (pinfunction "2_2") (pintype "passive"))
      (node (ref "R15") (pin "2") (pinfunction "2_2") (pintype "passive"))
      (node (ref "U2") (pin "D7") (pinfunction "AVSS_D7") (pintype "passive"))
    )
    (net (code "41") (name "Net-(U2-MUX_OUT)") (class "Default")
      (node (ref "R8") (pin "1") (pinfunction "1_1") (pintype "passive"))
      (node (ref "U2") (pin "C1") (pinfunction "MUX_OUT_C1") (pintype "passive"))
    )
    (net (code "42") (name "Net-(U3-+IN)") (class "Default")
      (node (ref "R10") (pin "2") (pinfunction "2_2") (pintype "passive"))
      (node (ref "R8") (pin "2") (pinfunction "2_2") (pintype "passive"))
      (node (ref "U3") (pin "3") (pinfunction "+IN_3") (pintype "passive"))
    )
    (net (code "43") (name "Net-(U3--IN)") (class "Default")
      (node (ref "R6") (pin "2") (pinfunction "2_2") (pintype "passive"))
      (node (ref "R7") (pin "1") (pinfunction "1_1") (pintype "passive"))
      (node (ref "U3") (pin "2") (pinfunction "-IN_2") (pintype "passive"))
    )
    (net (code "44") (name "Net-(U3-V+)") (class "Default")
      (node (ref "C11") (pin "2") (pinfunction "2_2") (pintype "passive"))
      (node (ref "C7") (pin "2") (pinfunction "2_2") (pintype "passive"))
      (node (ref "R4") (pin "1") (pinfunction "1_1") (pintype "passive"))
      (node (ref "U3") (pin "7") (pinfunction "V+_7") (pintype "passive"))
    )
    (net (code "45") (name "Net-(U3-V-)") (class "Default")
      (node (ref "C12") (pin "2") (pinfunction "2_2") (pintype "passive"))
      (node (ref "C13") (pin "2") (pinfunction "2_2") (pintype "passive"))
      (node (ref "R14") (pin "2") (pinfunction "2_2") (pintype "passive"))
      (node (ref "U3") (pin "4") (pinfunction "V-_4") (pintype "passive"))
    )
    (net (code "46") (name "Net-(U4-FB)") (class "Default")
      (node (ref "R2") (pin "1") (pinfunction "1_1") (pintype "passive"))
      (node (ref "R3") (pin "2") (pinfunction "2_2") (pintype "passive"))
      (node (ref "U4") (pin "2") (pinfunction "FB_2") (pintype "passive"))
    )
    (net (code "47") (name "Net-(U4-REF)") (class "Default")
      (node (ref "R1") (pin "1") (pinfunction "1_1") (pintype "passive"))
      (node (ref "U4") (pin "5") (pinfunction "REF_5") (pintype "passive"))
    )
    (net (code "48") (name "Net-(U5-ADCIN)") (class "Default")
      (node (ref "C30") (pin "1") (pinfunction "1_1") (pintype "passive"))
      (node (ref "R18") (pin "1") (pinfunction "1_1") (pintype "passive"))
      (node (ref "U5") (pin "14") (pinfunction "ADCIN_14") (pintype "passive"))
    )
    (net (code "49") (name "Net-(U5-AVDD)") (class "Default")
      (node (ref "C27") (pin "1") (pinfunction "1_1") (pintype "passive"))
      (node (ref "C28") (pin "1") (pinfunction "1_1") (pintype "passive"))
      (node (ref "R16") (pin "1") (pinfunction "1_1") (pintype "passive"))
      (node (ref "U5") (pin "15") (pinfunction "AVDD_15") (pintype "passive"))
    )
    (net (code "50") (name "Net-(U5-MUXOUT)") (class "Default")
      (node (ref "R18") (pin "2") (pinfunction "2_2") (pintype "passive"))
      (node (ref "U5") (pin "13") (pinfunction "MUXOUT_13") (pintype "passive"))
    )
    (net (code "51") (name "Net-(U7-COMP1)") (class "Default")
      (node (ref "U7") (pin "b7") (pinfunction "COMP1_b7") (pintype "passive"))
      (node (ref "U7") (pin "e7") (pinfunction "COMP2_e7") (pintype "passive"))
    )
    (net (code "52") (name "Net-(U7-COMP3)") (class "Default")
      (node (ref "U7") (pin "h7") (pinfunction "COMP3_h7") (pintype "passive"))
      (node (ref "U7") (pin "l7") (pinfunction "COMP4_l7") (pintype "passive"))
    )
    (net (code "53") (name "Net-(U7-FB1)") (class "Default")
      (node (ref "R9") (pin "2") (pinfunction "2_2") (pintype "passive"))
      (node (ref "U7") (pin "a7") (pinfunction "FB1_a7") (pintype "passive"))
      (node (ref "U7") (pin "d7") (pinfunction "FB2_d7") (pintype "passive"))
    )
    (net (code "54") (name "Net-(U7-FB3)") (class "Default")
      (node (ref "R11") (pin "2") (pinfunction "2_2") (pintype "passive"))
      (node (ref "U7") (pin "g7") (pinfunction "FB3_g7") (pintype "passive"))
      (node (ref "U7") (pin "j7") (pinfunction "FB4_j7") (pintype "passive"))
    )
    (net (code "55") (name "Net-(U7-INTVCC1)") (class "Default")
      (node (ref "U7") (pin "b6") (pinfunction "MODE1_b6") (pintype "passive"))
      (node (ref "U7") (pin "c4") (pinfunction "INTVCC1_c4") (pintype "passive"))
    )
    (net (code "56") (name "Net-(U7-INTVCC2)") (class "Default")
      (node (ref "U7") (pin "e6") (pinfunction "MODE2_e6") (pintype "passive"))
      (node (ref "U7") (pin "f4") (pinfunction "INTVCC2_f4") (pintype "passive"))
    )
    (net (code "57") (name "Net-(U7-INTVCC3)") (class "Default")
      (node (ref "U7") (pin "h6") (pinfunction "MODE3_h6") (pintype "passive"))
      (node (ref "U7") (pin "j4") (pinfunction "INTVCC3_j4") (pintype "passive"))
    )
    (net (code "58") (name "Net-(U7-INTVCC4)") (class "Default")
      (node (ref "U7") (pin "k5") (pinfunction "INTVCC4_k5") (pintype "passive"))
      (node (ref "U7") (pin "l6") (pinfunction "MODE4_l6") (pintype "passive"))
    )
    (net (code "59") (name "Net-(U7-TRACK{slash}SS1)") (class "Default")
      (node (ref "C16") (pin "2") (pinfunction "2_2") (pintype "passive"))
      (node (ref "U7") (pin "a6") (pinfunction "TRACK/SS1_a6") (pintype "passive"))
      (node (ref "U7") (pin "d6") (pinfunction "TRACK/SS2_d6") (pintype "passive"))
    )
    (net (code "60") (name "Net-(U7-TRACK{slash}SS3)") (class "Default")
      (node (ref "C18") (pin "2") (pinfunction "2_2") (pintype "passive"))
      (node (ref "U7") (pin "g6") (pinfunction "TRACK/SS3_g6") (pintype "passive"))
      (node (ref "U7") (pin "k6") (pinfunction "TRACK/SS4_k6") (pintype "passive"))
    )
    (net (code "61") (name "Net-(U8-Vin)") (class "Default")
      (node (ref "C37") (pin "2") (pinfunction "2_2") (pintype "passive"))
      (node (ref "C38") (pin "2") (pinfunction "2_2") (pintype "passive"))
      (node (ref "R19") (pin "2") (pinfunction "2_2") (pintype "passive"))
      (node (ref "U8") (pin "2") (pinfunction "Vin_2") (pintype "passive"))
    )
    (net (code "62") (name "unconnected-(U2-DNC-PadA1)") (class "Default")
      (node (ref "U2") (pin "A1") (pinfunction "DNC_A1") (pintype "passive"))
    )
    (net (code "63") (name "unconnected-(U2-DNC-PadA7)") (class "Default")
      (node (ref "U2") (pin "A7") (pinfunction "DNC_A7") (pintype "passive"))
    )
    (net (code "64") (name "unconnected-(U2-DNC-PadC5)") (class "Default")
      (node (ref "U2") (pin "C5") (pinfunction "DNC_C5") (pintype "passive"))
    )
    (net (code "65") (name "unconnected-(U2-DNC-PadG1)") (class "Default")
      (node (ref "U2") (pin "G1") (pinfunction "DNC_G1") (pintype "passive"))
    )
    (net (code "66") (name "unconnected-(U2-DNC-PadG7)") (class "Default")
      (node (ref "U2") (pin "G7") (pinfunction "DNC_G7") (pintype "passive"))
    )
    (net (code "67") (name "unconnected-(U2-Vout0-PadB3)") (class "Default")
      (node (ref "U2") (pin "B3") (pinfunction "Vout0_B3") (pintype "passive"))
    )
    (net (code "68") (name "unconnected-(U2-Vout3-PadB4)") (class "Default")
      (node (ref "U2") (pin "B4") (pinfunction "Vout3_B4") (pintype "passive"))
    )
    (net (code "69") (name "unconnected-(U2-Vout8-PadF5)") (class "Default")
      (node (ref "U2") (pin "F5") (pinfunction "Vout8_F5") (pintype "passive"))
    )
    (net (code "70") (name "unconnected-(U3-NC-Pad5)") (class "Default")
      (node (ref "U3") (pin "5") (pinfunction "NC_5") (pintype "passive"))
    )
    (net (code "71") (name "unconnected-(U3-NULL-Pad1)") (class "Default")
      (node (ref "U3") (pin "1") (pinfunction "NULL_1") (pintype "passive"))
    )
    (net (code "72") (name "unconnected-(U3-NULL-Pad8)") (class "Default")
      (node (ref "U3") (pin "8") (pinfunction "NULL_8") (pintype "passive"))
    )
    (net (code "73") (name "unconnected-(U5-PWRCON-Pad7)") (class "Default")
      (node (ref "U5") (pin "7") (pinfunction "PWRCON_7") (pintype "passive"))
    )
    (net (code "74") (name "unconnected-(U7-CLKIN-Padc7)") (class "Default")
      (node (ref "U7") (pin "c7") (pinfunction "CLKIN_c7") (pintype "passive"))
    )
    (net (code "75") (name "unconnected-(U7-CLKOUT-Padj3)") (class "Default")
      (node (ref "U7") (pin "j3") (pinfunction "CLKOUT_j3") (pintype "passive"))
    )
    (net (code "76") (name "unconnected-(U7-PGOOD1-Padc3)") (class "Default")
      (node (ref "U7") (pin "c3") (pinfunction "PGOOD1_c3") (pintype "passive"))
    )
    (net (code "77") (name "unconnected-(U7-PGOOD2-Padc2)") (class "Default")
      (node (ref "U7") (pin "c2") (pinfunction "PGOOD2_c2") (pintype "passive"))
    )
    (net (code "78") (name "unconnected-(U7-PGOOD3-Padf2)") (class "Default")
      (node (ref "U7") (pin "f2") (pinfunction "PGOOD3_f2") (pintype "passive"))
    )
    (net (code "79") (name "unconnected-(U7-PGOOD4-Padj2)") (class "Default")
      (node (ref "U7") (pin "j2") (pinfunction "PGOOD4_j2") (pintype "passive"))
    )
    (net (code "80") (name "unconnected-(U7-VOUT2-Padc1)") (class "Default")
      (node (ref "U7") (pin "c1") (pinfunction "VOUT2_c1") (pintype "passive"))
    )
    (net (code "81") (name "unconnected-(U7-VOUT2-Padd1)") (class "Default")
      (node (ref "U7") (pin "d1") (pinfunction "VOUT2_d1") (pintype "passive"))
    )
    (net (code "82") (name "unconnected-(U7-VOUT2-Padd2)") (class "Default")
      (node (ref "U7") (pin "d2") (pinfunction "VOUT2_d2") (pintype "passive"))
    )
    (net (code "83") (name "unconnected-(U7-VOUT4-Padj1)") (class "Default")
      (node (ref "U7") (pin "j1") (pinfunction "VOUT4_j1") (pintype "passive"))
    )
    (net (code "84") (name "unconnected-(U7-VOUT4-Padk1)") (class "Default")
      (node (ref "U7") (pin "k1") (pinfunction "VOUT4_k1") (pintype "passive"))
    )
    (net (code "85") (name "unconnected-(U7-VOUT4-Padk2)") (class "Default")
      (node (ref "U7") (pin "k2") (pinfunction "VOUT4_k2") (pintype "passive"))
    )
    (net (code "86") (name "unconnected-(U8-DNC-Pad8)") (class "Default")
      (node (ref "U8") (pin "8") (pinfunction "DNC_8") (pintype "passive"))
    )
    (net (code "87") (name "unconnected-(U8-NIC-Pad1)") (class "Default")
      (node (ref "U8") (pin "1") (pinfunction "NIC_1") (pintype "passive"))
    )
  )
)
